# WheelPCB.net
KiCad netlist of a schematic drawn in EAGLE
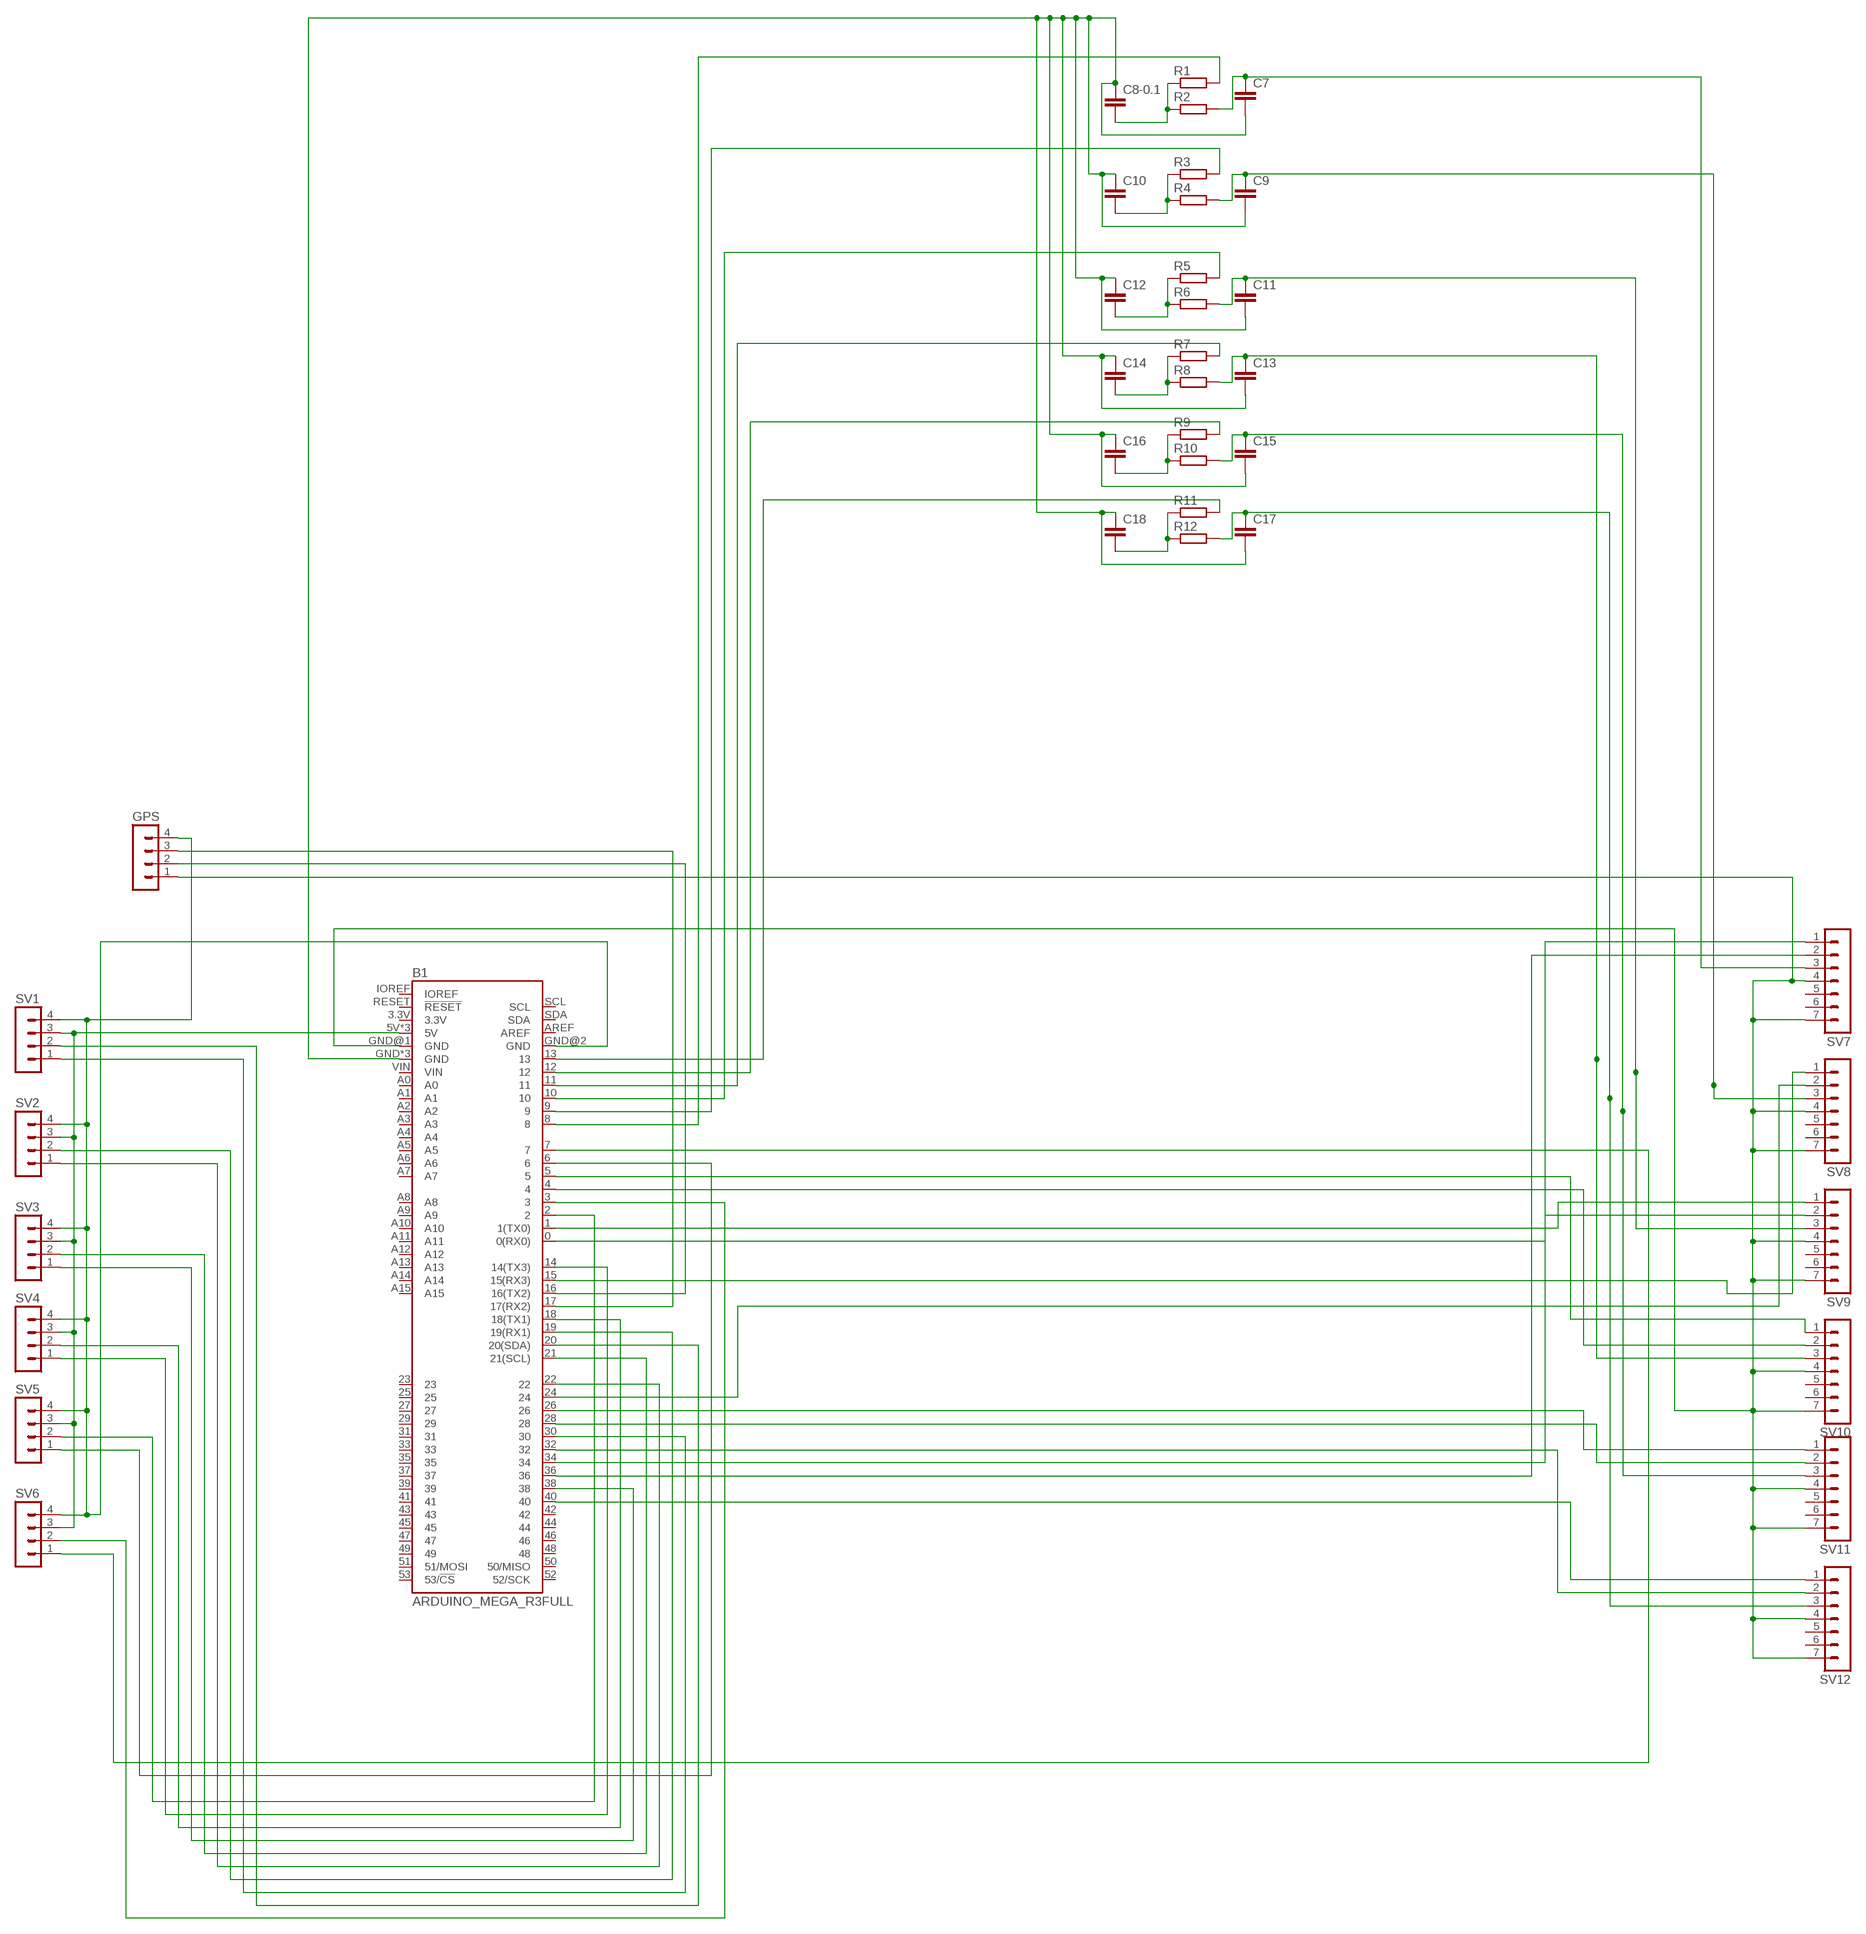
[diagram p0: schematic, sheet 1]

(export (version "E")
  (design (tool "Eeschema 10.0.6"))
  (components
    (comp (ref "B1")
      (value "ARDUINO_MEGA_R3FULL")
      (footprint "eagle-import:ARDUINO_MEGA_NO_SILK")
      (libsource (lib "eagle-import") (part "ARDUINO_MEGA_R3FULL"))
    )
    (comp (ref "C7")
      (value "C2.5/5")
      (footprint "eagle-import:C2.5-5")
      (libsource (lib "eagle-import") (part "C2.5/5"))
    )
    (comp (ref "C8-0.1")
      (value "C2.5/5")
      (footprint "eagle-import:C2.5-5")
      (libsource (lib "eagle-import") (part "C2.5/5"))
    )
    (comp (ref "C9")
      (value "C2.5/5")
      (footprint "eagle-import:C2.5-5")
      (libsource (lib "eagle-import") (part "C2.5/5"))
    )
    (comp (ref "C10")
      (value "C2.5/5")
      (footprint "eagle-import:C2.5-5")
      (libsource (lib "eagle-import") (part "C2.5/5"))
    )
    (comp (ref "C11")
      (value "C2.5/5")
      (footprint "eagle-import:C2.5-5")
      (libsource (lib "eagle-import") (part "C2.5/5"))
    )
    (comp (ref "C12")
      (value "C2.5/5")
      (footprint "eagle-import:C2.5-5")
      (libsource (lib "eagle-import") (part "C2.5/5"))
    )
    (comp (ref "C13")
      (value "C2.5/5")
      (footprint "eagle-import:C2.5-5")
      (libsource (lib "eagle-import") (part "C2.5/5"))
    )
    (comp (ref "C14")
      (value "C2.5/5")
      (footprint "eagle-import:C2.5-5")
      (libsource (lib "eagle-import") (part "C2.5/5"))
    )
    (comp (ref "C15")
      (value "C2.5/5")
      (footprint "eagle-import:C2.5-5")
      (libsource (lib "eagle-import") (part "C2.5/5"))
    )
    (comp (ref "C16")
      (value "C2.5/5")
      (footprint "eagle-import:C2.5-5")
      (libsource (lib "eagle-import") (part "C2.5/5"))
    )
    (comp (ref "C17")
      (value "C2.5/5")
      (footprint "eagle-import:C2.5-5")
      (libsource (lib "eagle-import") (part "C2.5/5"))
    )
    (comp (ref "C18")
      (value "C2.5/5")
      (footprint "eagle-import:C2.5-5")
      (libsource (lib "eagle-import") (part "C2.5/5"))
    )
    (comp (ref "GPS")
      (value "MA04-1")
      (footprint "eagle-import:MA04-1")
      (libsource (lib "eagle-import") (part "MA04-1"))
    )
    (comp (ref "R1")
      (value "R-EU_0207/10")
      (footprint "eagle-import:0207_10")
      (libsource (lib "eagle-import") (part "R-EU_0207/10"))
    )
    (comp (ref "R2")
      (value "R-EU_0207/10")
      (footprint "eagle-import:0207_10")
      (libsource (lib "eagle-import") (part "R-EU_0207/10"))
    )
    (comp (ref "R3")
      (value "R-EU_0207/10")
      (footprint "eagle-import:0207_10")
      (libsource (lib "eagle-import") (part "R-EU_0207/10"))
    )
    (comp (ref "R4")
      (value "R-EU_0207/10")
      (footprint "eagle-import:0207_10")
      (libsource (lib "eagle-import") (part "R-EU_0207/10"))
    )
    (comp (ref "R5")
      (value "R-EU_0207/10")
      (footprint "eagle-import:0207_10")
      (libsource (lib "eagle-import") (part "R-EU_0207/10"))
    )
    (comp (ref "R6")
      (value "R-EU_0207/10")
      (footprint "eagle-import:0207_10")
      (libsource (lib "eagle-import") (part "R-EU_0207/10"))
    )
    (comp (ref "R7")
      (value "R-EU_0207/10")
      (footprint "eagle-import:0207_10")
      (libsource (lib "eagle-import") (part "R-EU_0207/10"))
    )
    (comp (ref "R8")
      (value "R-EU_0207/10")
      (footprint "eagle-import:0207_10")
      (libsource (lib "eagle-import") (part "R-EU_0207/10"))
    )
    (comp (ref "R9")
      (value "R-EU_0207/10")
      (footprint "eagle-import:0207_10")
      (libsource (lib "eagle-import") (part "R-EU_0207/10"))
    )
    (comp (ref "R10")
      (value "R-EU_0207/10")
      (footprint "eagle-import:0207_10")
      (libsource (lib "eagle-import") (part "R-EU_0207/10"))
    )
    (comp (ref "R11")
      (value "R-EU_0207/10")
      (footprint "eagle-import:0207_10")
      (libsource (lib "eagle-import") (part "R-EU_0207/10"))
    )
    (comp (ref "R12")
      (value "R-EU_0207/10")
      (footprint "eagle-import:0207_10")
      (libsource (lib "eagle-import") (part "R-EU_0207/10"))
    )
    (comp (ref "SV1")
      (value "MA04-1")
      (footprint "eagle-import:MA04-1")
      (libsource (lib "eagle-import") (part "MA04-1"))
    )
    (comp (ref "SV2")
      (value "MA04-1")
      (footprint "eagle-import:MA04-1")
      (libsource (lib "eagle-import") (part "MA04-1"))
    )
    (comp (ref "SV3")
      (value "MA04-1")
      (footprint "eagle-import:MA04-1")
      (libsource (lib "eagle-import") (part "MA04-1"))
    )
    (comp (ref "SV4")
      (value "MA04-1")
      (footprint "eagle-import:MA04-1")
      (libsource (lib "eagle-import") (part "MA04-1"))
    )
    (comp (ref "SV5")
      (value "MA04-1")
      (footprint "eagle-import:MA04-1")
      (libsource (lib "eagle-import") (part "MA04-1"))
    )
    (comp (ref "SV6")
      (value "MA04-1")
      (footprint "eagle-import:MA04-1")
      (libsource (lib "eagle-import") (part "MA04-1"))
    )
    (comp (ref "SV7")
      (value "MA07-1")
      (footprint "eagle-import:MA07-1")
      (libsource (lib "eagle-import") (part "MA07-1"))
    )
    (comp (ref "SV8")
      (value "MA07-1")
      (footprint "eagle-import:MA07-1")
      (libsource (lib "eagle-import") (part "MA07-1"))
    )
    (comp (ref "SV9")
      (value "MA07-1")
      (footprint "eagle-import:MA07-1")
      (libsource (lib "eagle-import") (part "MA07-1"))
    )
    (comp (ref "SV10")
      (value "MA07-1")
      (footprint "eagle-import:MA07-1")
      (libsource (lib "eagle-import") (part "MA07-1"))
    )
    (comp (ref "SV11")
      (value "MA07-1")
      (footprint "eagle-import:MA07-1")
      (libsource (lib "eagle-import") (part "MA07-1"))
    )
    (comp (ref "SV12")
      (value "MA07-1")
      (footprint "eagle-import:MA07-1")
      (libsource (lib "eagle-import") (part "MA07-1"))
    )
  )
  (nets
    (net (code "1") (name "Net-(B1-0(RX0))") (class "Default")
      (node (ref "B1") (pin "0") (pinfunction "0(RX0)_0") (pintype "bidirectional"))
      (node (ref "SV9") (pin "2") (pinfunction "2_2") (pintype "passive"))
    )
    (net (code "2") (name "Net-(B1-1(TX0))") (class "Default")
      (node (ref "B1") (pin "1") (pinfunction "1(TX0)_1") (pintype "bidirectional"))
      (node (ref "SV9") (pin "1") (pinfunction "1_1") (pintype "passive"))
    )
    (net (code "3") (name "Net-(B1-5V-Pad5V@1)") (class "Default")
      (node (ref "B1") (pin "5V") (pinfunction "5V_5V") (pintype "bidirectional"))
      (node (ref "B1") (pin "5V@1") (pinfunction "5V_5V@1") (pintype "bidirectional"))
      (node (ref "B1") (pin "5V@2") (pinfunction "5V_5V@2") (pintype "bidirectional"))
      (node (ref "SV1") (pin "3") (pinfunction "3_3") (pintype "passive"))
      (node (ref "SV2") (pin "3") (pinfunction "3_3") (pintype "passive"))
      (node (ref "SV3") (pin "3") (pinfunction "3_3") (pintype "passive"))
      (node (ref "SV4") (pin "3") (pinfunction "3_3") (pintype "passive"))
      (node (ref "SV5") (pin "3") (pinfunction "3_3") (pintype "passive"))
      (node (ref "SV6") (pin "3") (pinfunction "3_3") (pintype "passive"))
    )
    (net (code "4") (name "Net-(B1-14(TX3))") (class "Default")
      (node (ref "B1") (pin "14") (pinfunction "14(TX3)_14") (pintype "bidirectional"))
      (node (ref "SV4") (pin "1") (pinfunction "1_1") (pintype "passive"))
    )
    (net (code "5") (name "Net-(B1-15(RX3))") (class "Default")
      (node (ref "B1") (pin "15") (pinfunction "15(RX3)_15") (pintype "bidirectional"))
      (node (ref "SV8") (pin "1") (pinfunction "1_1") (pintype "passive"))
    )
    (net (code "6") (name "Net-(B1-16(TX2))") (class "Default")
      (node (ref "B1") (pin "16") (pinfunction "16(TX2)_16") (pintype "bidirectional"))
      (node (ref "GPS") (pin "2") (pinfunction "2_2") (pintype "passive"))
    )
    (net (code "7") (name "Net-(B1-17(RX2))") (class "Default")
      (node (ref "B1") (pin "17") (pinfunction "17(RX2)_17") (pintype "bidirectional"))
      (node (ref "GPS") (pin "3") (pinfunction "3_3") (pintype "passive"))
    )
    (net (code "8") (name "Net-(B1-18(TX1))") (class "Default")
      (node (ref "B1") (pin "18") (pinfunction "18(TX1)_18") (pintype "bidirectional"))
      (node (ref "SV4") (pin "2") (pinfunction "2_2") (pintype "passive"))
    )
    (net (code "9") (name "Net-(B1-19(RX1))") (class "Default")
      (node (ref "B1") (pin "19") (pinfunction "19(RX1)_19") (pintype "bidirectional"))
      (node (ref "SV2") (pin "2") (pinfunction "2_2") (pintype "passive"))
    )
    (net (code "10") (name "Net-(B1-20(SDA))") (class "Default")
      (node (ref "B1") (pin "20") (pinfunction "20(SDA)_20") (pintype "bidirectional"))
      (node (ref "SV1") (pin "2") (pinfunction "2_2") (pintype "passive"))
    )
    (net (code "11") (name "Net-(B1-21(SCL))") (class "Default")
      (node (ref "B1") (pin "21") (pinfunction "21(SCL)_21") (pintype "bidirectional"))
      (node (ref "SV3") (pin "2") (pinfunction "2_2") (pintype "passive"))
    )
    (net (code "12") (name "Net-(B1-GND-PadGND@1)") (class "Default")
      (node (ref "B1") (pin "GND@1") (pinfunction "GND_GND@1") (pintype "bidirectional"))
      (node (ref "GPS") (pin "1") (pinfunction "1_1") (pintype "passive"))
      (node (ref "SV10") (pin "4") (pinfunction "4_4") (pintype "passive"))
      (node (ref "SV10") (pin "7") (pinfunction "7_7") (pintype "passive"))
      (node (ref "SV11") (pin "4") (pinfunction "4_4") (pintype "passive"))
      (node (ref "SV11") (pin "7") (pinfunction "7_7") (pintype "passive"))
      (node (ref "SV12") (pin "4") (pinfunction "4_4") (pintype "passive"))
      (node (ref "SV12") (pin "7") (pinfunction "7_7") (pintype "passive"))
      (node (ref "SV7") (pin "4") (pinfunction "4_4") (pintype "passive"))
      (node (ref "SV7") (pin "7") (pinfunction "7_7") (pintype "passive"))
      (node (ref "SV8") (pin "4") (pinfunction "4_4") (pintype "passive"))
      (node (ref "SV8") (pin "7") (pinfunction "7_7") (pintype "passive"))
      (node (ref "SV9") (pin "4") (pinfunction "4_4") (pintype "passive"))
      (node (ref "SV9") (pin "7") (pinfunction "7_7") (pintype "passive"))
    )
    (net (code "13") (name "Net-(B1-GND-PadGND@2)") (class "Default")
      (node (ref "B1") (pin "GND@2") (pinfunction "GND_GND@2") (pintype "bidirectional"))
      (node (ref "GPS") (pin "4") (pinfunction "4_4") (pintype "passive"))
      (node (ref "SV1") (pin "4") (pinfunction "4_4") (pintype "passive"))
      (node (ref "SV2") (pin "4") (pinfunction "4_4") (pintype "passive"))
      (node (ref "SV3") (pin "4") (pinfunction "4_4") (pintype "passive"))
      (node (ref "SV4") (pin "4") (pinfunction "4_4") (pintype "passive"))
      (node (ref "SV5") (pin "4") (pinfunction "4_4") (pintype "passive"))
      (node (ref "SV6") (pin "4") (pinfunction "4_4") (pintype "passive"))
    )
    (net (code "14") (name "Net-(B1-GND-PadGND@3)") (class "Default")
      (node (ref "B1") (pin "GND") (pinfunction "GND_GND") (pintype "bidirectional"))
      (node (ref "B1") (pin "GND@3") (pinfunction "GND_GND@3") (pintype "bidirectional"))
      (node (ref "B1") (pin "GND@4") (pinfunction "GND_GND@4") (pintype "bidirectional"))
      (node (ref "C10") (pin "1") (pinfunction "1_1") (pintype "passive"))
      (node (ref "C11") (pin "2") (pinfunction "2_2") (pintype "passive"))
      (node (ref "C12") (pin "1") (pinfunction "1_1") (pintype "passive"))
      (node (ref "C13") (pin "2") (pinfunction "2_2") (pintype "passive"))
      (node (ref "C14") (pin "1") (pinfunction "1_1") (pintype "passive"))
      (node (ref "C15") (pin "2") (pinfunction "2_2") (pintype "passive"))
      (node (ref "C16") (pin "1") (pinfunction "1_1") (pintype "passive"))
      (node (ref "C17") (pin "2") (pinfunction "2_2") (pintype "passive"))
      (node (ref "C18") (pin "1") (pinfunction "1_1") (pintype "passive"))
      (node (ref "C7") (pin "2") (pinfunction "2_2") (pintype "passive"))
      (node (ref "C8-0.1") (pin "1") (pinfunction "1_1") (pintype "passive"))
      (node (ref "C9") (pin "2") (pinfunction "2_2") (pintype "passive"))
    )
    (net (code "15") (name "Net-(B1-Pad2)") (class "Default")
      (node (ref "B1") (pin "2") (pinfunction "2_2") (pintype "bidirectional"))
      (node (ref "SV5") (pin "2") (pinfunction "2_2") (pintype "passive"))
    )
    (net (code "16") (name "Net-(B1-Pad3)") (class "Default")
      (node (ref "B1") (pin "3") (pinfunction "3_3") (pintype "bidirectional"))
      (node (ref "SV6") (pin "2") (pinfunction "2_2") (pintype "passive"))
    )
    (net (code "17") (name "Net-(B1-Pad4)") (class "Default")
      (node (ref "B1") (pin "4") (pinfunction "4_4") (pintype "bidirectional"))
      (node (ref "SV10") (pin "2") (pinfunction "2_2") (pintype "passive"))
    )
    (net (code "18") (name "Net-(B1-Pad5)") (class "Default")
      (node (ref "B1") (pin "5") (pinfunction "5_5") (pintype "bidirectional"))
      (node (ref "SV10") (pin "1") (pinfunction "1_1") (pintype "passive"))
    )
    (net (code "19") (name "Net-(B1-Pad6)") (class "Default")
      (node (ref "B1") (pin "6") (pinfunction "6_6") (pintype "bidirectional"))
      (node (ref "SV5") (pin "1") (pinfunction "1_1") (pintype "passive"))
    )
    (net (code "20") (name "Net-(B1-Pad7)") (class "Default")
      (node (ref "B1") (pin "7") (pinfunction "7_7") (pintype "bidirectional"))
      (node (ref "SV6") (pin "1") (pinfunction "1_1") (pintype "passive"))
    )
    (net (code "21") (name "Net-(B1-Pad8)") (class "Default")
      (node (ref "B1") (pin "8") (pinfunction "8_8") (pintype "bidirectional"))
      (node (ref "R1") (pin "2") (pinfunction "2_2") (pintype "passive"))
    )
    (net (code "22") (name "Net-(B1-Pad9)") (class "Default")
      (node (ref "B1") (pin "9") (pinfunction "9_9") (pintype "bidirectional"))
      (node (ref "R3") (pin "2") (pinfunction "2_2") (pintype "passive"))
    )
    (net (code "23") (name "Net-(B1-Pad10)") (class "Default")
      (node (ref "B1") (pin "10") (pinfunction "10_10") (pintype "bidirectional"))
      (node (ref "R5") (pin "2") (pinfunction "2_2") (pintype "passive"))
    )
    (net (code "24") (name "Net-(B1-Pad11)") (class "Default")
      (node (ref "B1") (pin "11") (pinfunction "11_11") (pintype "bidirectional"))
      (node (ref "R7") (pin "2") (pinfunction "2_2") (pintype "passive"))
    )
    (net (code "25") (name "Net-(B1-Pad12)") (class "Default")
      (node (ref "B1") (pin "12") (pinfunction "12_12") (pintype "bidirectional"))
      (node (ref "R9") (pin "2") (pinfunction "2_2") (pintype "passive"))
    )
    (net (code "26") (name "Net-(B1-Pad13)") (class "Default")
      (node (ref "B1") (pin "13") (pinfunction "13_13") (pintype "bidirectional"))
      (node (ref "R11") (pin "2") (pinfunction "2_2") (pintype "passive"))
    )
    (net (code "27") (name "Net-(B1-Pad22)") (class "Default")
      (node (ref "B1") (pin "22") (pinfunction "22_22") (pintype "bidirectional"))
      (node (ref "SV2") (pin "1") (pinfunction "1_1") (pintype "passive"))
    )
    (net (code "28") (name "Net-(B1-Pad24)") (class "Default")
      (node (ref "B1") (pin "24") (pinfunction "24_24") (pintype "bidirectional"))
      (node (ref "SV8") (pin "2") (pinfunction "2_2") (pintype "passive"))
    )
    (net (code "29") (name "Net-(B1-Pad26)") (class "Default")
      (node (ref "B1") (pin "26") (pinfunction "26_26") (pintype "bidirectional"))
      (node (ref "SV11") (pin "1") (pinfunction "1_1") (pintype "passive"))
    )
    (net (code "30") (name "Net-(B1-Pad28)") (class "Default")
      (node (ref "B1") (pin "28") (pinfunction "28_28") (pintype "bidirectional"))
      (node (ref "SV11") (pin "2") (pinfunction "2_2") (pintype "passive"))
    )
    (net (code "31") (name "Net-(B1-Pad30)") (class "Default")
      (node (ref "B1") (pin "30") (pinfunction "30_30") (pintype "bidirectional"))
      (node (ref "SV1") (pin "1") (pinfunction "1_1") (pintype "passive"))
    )
    (net (code "32") (name "Net-(B1-Pad32)") (class "Default")
      (node (ref "B1") (pin "32") (pinfunction "32_32") (pintype "bidirectional"))
      (node (ref "SV12") (pin "2") (pinfunction "2_2") (pintype "passive"))
    )
    (net (code "33") (name "Net-(B1-Pad34)") (class "Default")
      (node (ref "B1") (pin "34") (pinfunction "34_34") (pintype "bidirectional"))
      (node (ref "SV7") (pin "1") (pinfunction "1_1") (pintype "passive"))
    )
    (net (code "34") (name "Net-(B1-Pad36)") (class "Default")
      (node (ref "B1") (pin "36") (pinfunction "36_36") (pintype "bidirectional"))
      (node (ref "SV7") (pin "2") (pinfunction "2_2") (pintype "passive"))
    )
    (net (code "35") (name "Net-(B1-Pad38)") (class "Default")
      (node (ref "B1") (pin "38") (pinfunction "38_38") (pintype "bidirectional"))
      (node (ref "SV3") (pin "1") (pinfunction "1_1") (pintype "passive"))
    )
    (net (code "36") (name "Net-(B1-Pad40)") (class "Default")
      (node (ref "B1") (pin "40") (pinfunction "40_40") (pintype "bidirectional"))
      (node (ref "SV12") (pin "1") (pinfunction "1_1") (pintype "passive"))
    )
    (net (code "37") (name "Net-(C7-Pad1)") (class "Default")
      (node (ref "C7") (pin "1") (pinfunction "1_1") (pintype "passive"))
      (node (ref "R2") (pin "2") (pinfunction "2_2") (pintype "passive"))
      (node (ref "SV7") (pin "3") (pinfunction "3_3") (pintype "passive"))
    )
    (net (code "38") (name "Net-(C8-0.1-Pad2)") (class "Default")
      (node (ref "C8-0.1") (pin "2") (pinfunction "2_2") (pintype "passive"))
      (node (ref "R1") (pin "1") (pinfunction "1_1") (pintype "passive"))
      (node (ref "R2") (pin "1") (pinfunction "1_1") (pintype "passive"))
    )
    (net (code "39") (name "Net-(C9-Pad1)") (class "Default")
      (node (ref "C9") (pin "1") (pinfunction "1_1") (pintype "passive"))
      (node (ref "R4") (pin "2") (pinfunction "2_2") (pintype "passive"))
      (node (ref "SV8") (pin "3") (pinfunction "3_3") (pintype "passive"))
    )
    (net (code "40") (name "Net-(C10-Pad2)") (class "Default")
      (node (ref "C10") (pin "2") (pinfunction "2_2") (pintype "passive"))
      (node (ref "R3") (pin "1") (pinfunction "1_1") (pintype "passive"))
      (node (ref "R4") (pin "1") (pinfunction "1_1") (pintype "passive"))
    )
    (net (code "41") (name "Net-(C11-Pad1)") (class "Default")
      (node (ref "C11") (pin "1") (pinfunction "1_1") (pintype "passive"))
      (node (ref "R6") (pin "2") (pinfunction "2_2") (pintype "passive"))
      (node (ref "SV9") (pin "3") (pinfunction "3_3") (pintype "passive"))
    )
    (net (code "42") (name "Net-(C12-Pad2)") (class "Default")
      (node (ref "C12") (pin "2") (pinfunction "2_2") (pintype "passive"))
      (node (ref "R5") (pin "1") (pinfunction "1_1") (pintype "passive"))
      (node (ref "R6") (pin "1") (pinfunction "1_1") (pintype "passive"))
    )
    (net (code "43") (name "Net-(C13-Pad1)") (class "Default")
      (node (ref "C13") (pin "1") (pinfunction "1_1") (pintype "passive"))
      (node (ref "R8") (pin "2") (pinfunction "2_2") (pintype "passive"))
      (node (ref "SV10") (pin "3") (pinfunction "3_3") (pintype "passive"))
    )
    (net (code "44") (name "Net-(C14-Pad2)") (class "Default")
      (node (ref "C14") (pin "2") (pinfunction "2_2") (pintype "passive"))
      (node (ref "R7") (pin "1") (pinfunction "1_1") (pintype "passive"))
      (node (ref "R8") (pin "1") (pinfunction "1_1") (pintype "passive"))
    )
    (net (code "45") (name "Net-(C15-Pad1)") (class "Default")
      (node (ref "C15") (pin "1") (pinfunction "1_1") (pintype "passive"))
      (node (ref "R10") (pin "2") (pinfunction "2_2") (pintype "passive"))
      (node (ref "SV11") (pin "3") (pinfunction "3_3") (pintype "passive"))
    )
    (net (code "46") (name "Net-(C16-Pad2)") (class "Default")
      (node (ref "C16") (pin "2") (pinfunction "2_2") (pintype "passive"))
      (node (ref "R10") (pin "1") (pinfunction "1_1") (pintype "passive"))
      (node (ref "R9") (pin "1") (pinfunction "1_1") (pintype "passive"))
    )
    (net (code "47") (name "Net-(C17-Pad1)") (class "Default")
      (node (ref "C17") (pin "1") (pinfunction "1_1") (pintype "passive"))
      (node (ref "R12") (pin "2") (pinfunction "2_2") (pintype "passive"))
      (node (ref "SV12") (pin "3") (pinfunction "3_3") (pintype "passive"))
    )
    (net (code "48") (name "Net-(C18-Pad2)") (class "Default")
      (node (ref "C18") (pin "2") (pinfunction "2_2") (pintype "passive"))
      (node (ref "R11") (pin "1") (pinfunction "1_1") (pintype "passive"))
      (node (ref "R12") (pin "1") (pinfunction "1_1") (pintype "passive"))
    )
    (net (code "49") (name "unconnected-(B1-50{slash}MISO-Pad50)") (class "Default")
      (node (ref "B1") (pin "50") (pinfunction "50/MISO_50") (pintype "bidirectional"))
    )
    (net (code "50") (name "unconnected-(B1-51{slash}MOSI-Pad51)") (class "Default")
      (node (ref "B1") (pin "51") (pinfunction "51/MOSI_51") (pintype "bidirectional"))
    )
    (net (code "51") (name "unconnected-(B1-52{slash}SCK-Pad52)") (class "Default")
      (node (ref "B1") (pin "52") (pinfunction "52/SCK_52") (pintype "bidirectional"))
    )
    (net (code "52") (name "unconnected-(B1-53{slash}~{CS}-Pad53)") (class "Default")
      (node (ref "B1") (pin "53") (pinfunction "53/~{CS}_53") (pintype "bidirectional"))
    )
    (net (code "53") (name "unconnected-(B1-Pad3.3V)") (class "Default")
      (node (ref "B1") (pin "3.3V") (pinfunction "3.3V_3.3V") (pintype "bidirectional"))
    )
    (net (code "54") (name "unconnected-(B1-Pad23)") (class "Default")
      (node (ref "B1") (pin "23") (pinfunction "23_23") (pintype "bidirectional"))
    )
    (net (code "55") (name "unconnected-(B1-Pad25)") (class "Default")
      (node (ref "B1") (pin "25") (pinfunction "25_25") (pintype "bidirectional"))
    )
    (net (code "56") (name "unconnected-(B1-Pad27)") (class "Default")
      (node (ref "B1") (pin "27") (pinfunction "27_27") (pintype "bidirectional"))
    )
    (net (code "57") (name "unconnected-(B1-Pad29)") (class "Default")
      (node (ref "B1") (pin "29") (pinfunction "29_29") (pintype "bidirectional"))
    )
    (net (code "58") (name "unconnected-(B1-Pad31)") (class "Default")
      (node (ref "B1") (pin "31") (pinfunction "31_31") (pintype "bidirectional"))
    )
    (net (code "59") (name "unconnected-(B1-Pad33)") (class "Default")
      (node (ref "B1") (pin "33") (pinfunction "33_33") (pintype "bidirectional"))
    )
    (net (code "60") (name "unconnected-(B1-Pad35)") (class "Default")
      (node (ref "B1") (pin "35") (pinfunction "35_35") (pintype "bidirectional"))
    )
    (net (code "61") (name "unconnected-(B1-Pad37)") (class "Default")
      (node (ref "B1") (pin "37") (pinfunction "37_37") (pintype "bidirectional"))
    )
    (net (code "62") (name "unconnected-(B1-Pad39)") (class "Default")
      (node (ref "B1") (pin "39") (pinfunction "39_39") (pintype "bidirectional"))
    )
    (net (code "63") (name "unconnected-(B1-Pad41)") (class "Default")
      (node (ref "B1") (pin "41") (pinfunction "41_41") (pintype "bidirectional"))
    )
    (net (code "64") (name "unconnected-(B1-Pad42)") (class "Default")
      (node (ref "B1") (pin "42") (pinfunction "42_42") (pintype "bidirectional"))
    )
    (net (code "65") (name "unconnected-(B1-Pad43)") (class "Default")
      (node (ref "B1") (pin "43") (pinfunction "43_43") (pintype "bidirectional"))
    )
    (net (code "66") (name "unconnected-(B1-Pad44)") (class "Default")
      (node (ref "B1") (pin "44") (pinfunction "44_44") (pintype "bidirectional"))
    )
    (net (code "67") (name "unconnected-(B1-Pad45)") (class "Default")
      (node (ref "B1") (pin "45") (pinfunction "45_45") (pintype "bidirectional"))
    )
    (net (code "68") (name "unconnected-(B1-Pad46)") (class "Default")
      (node (ref "B1") (pin "46") (pinfunction "46_46") (pintype "bidirectional"))
    )
    (net (code "69") (name "unconnected-(B1-Pad47)") (class "Default")
      (node (ref "B1") (pin "47") (pinfunction "47_47") (pintype "bidirectional"))
    )
    (net (code "70") (name "unconnected-(B1-Pad48)") (class "Default")
      (node (ref "B1") (pin "48") (pinfunction "48_48") (pintype "bidirectional"))
    )
    (net (code "71") (name "unconnected-(B1-Pad49)") (class "Default")
      (node (ref "B1") (pin "49") (pinfunction "49_49") (pintype "bidirectional"))
    )
    (net (code "72") (name "unconnected-(B1-PadA0)") (class "Default")
      (node (ref "B1") (pin "A0") (pinfunction "A0_A0") (pintype "bidirectional"))
    )
    (net (code "73") (name "unconnected-(B1-PadA1)") (class "Default")
      (node (ref "B1") (pin "A1") (pinfunction "A1_A1") (pintype "bidirectional"))
    )
    (net (code "74") (name "unconnected-(B1-PadA2)") (class "Default")
      (node (ref "B1") (pin "A2") (pinfunction "A2_A2") (pintype "bidirectional"))
    )
    (net (code "75") (name "unconnected-(B1-PadA3)") (class "Default")
      (node (ref "B1") (pin "A3") (pinfunction "A3_A3") (pintype "bidirectional"))
    )
    (net (code "76") (name "unconnected-(B1-PadA4)") (class "Default")
      (node (ref "B1") (pin "A4") (pinfunction "A4_A4") (pintype "bidirectional"))
    )
    (net (code "77") (name "unconnected-(B1-PadA5)") (class "Default")
      (node (ref "B1") (pin "A5") (pinfunction "A5_A5") (pintype "bidirectional"))
    )
    (net (code "78") (name "unconnected-(B1-PadA6)") (class "Default")
      (node (ref "B1") (pin "A6") (pinfunction "A6_A6") (pintype "bidirectional"))
    )
    (net (code "79") (name "unconnected-(B1-PadA7)") (class "Default")
      (node (ref "B1") (pin "A7") (pinfunction "A7_A7") (pintype "bidirectional"))
    )
    (net (code "80") (name "unconnected-(B1-PadA8)") (class "Default")
      (node (ref "B1") (pin "A8") (pinfunction "A8_A8") (pintype "bidirectional"))
    )
    (net (code "81") (name "unconnected-(B1-PadA9)") (class "Default")
      (node (ref "B1") (pin "A9") (pinfunction "A9_A9") (pintype "bidirectional"))
    )
    (net (code "82") (name "unconnected-(B1-PadA10)") (class "Default")
      (node (ref "B1") (pin "A10") (pinfunction "A10_A10") (pintype "bidirectional"))
    )
    (net (code "83") (name "unconnected-(B1-PadA11)") (class "Default")
      (node (ref "B1") (pin "A11") (pinfunction "A11_A11") (pintype "bidirectional"))
    )
    (net (code "84") (name "unconnected-(B1-PadA12)") (class "Default")
      (node (ref "B1") (pin "A12") (pinfunction "A12_A12") (pintype "bidirectional"))
    )
    (net (code "85") (name "unconnected-(B1-PadA13)") (class "Default")
      (node (ref "B1") (pin "A13") (pinfunction "A13_A13") (pintype "bidirectional"))
    )
    (net (code "86") (name "unconnected-(B1-PadA14)") (class "Default")
      (node (ref "B1") (pin "A14") (pinfunction "A14_A14") (pintype "bidirectional"))
    )
    (net (code "87") (name "unconnected-(B1-PadA15)") (class "Default")
      (node (ref "B1") (pin "A15") (pinfunction "A15_A15") (pintype "bidirectional"))
    )
    (net (code "88") (name "unconnected-(B1-PadAREF)") (class "Default")
      (node (ref "B1") (pin "AREF") (pinfunction "AREF_AREF") (pintype "bidirectional"))
    )
    (net (code "89") (name "unconnected-(B1-PadIOREF)") (class "Default")
      (node (ref "B1") (pin "IOREF") (pinfunction "IOREF_IOREF") (pintype "bidirectional"))
    )
    (net (code "90") (name "unconnected-(B1-PadSCL)") (class "Default")
      (node (ref "B1") (pin "SCL") (pinfunction "SCL_SCL") (pintype "bidirectional"))
    )
    (net (code "91") (name "unconnected-(B1-PadSDA)") (class "Default")
      (node (ref "B1") (pin "SDA") (pinfunction "SDA_SDA") (pintype "bidirectional"))
    )
    (net (code "92") (name "unconnected-(B1-PadVIN)") (class "Default")
      (node (ref "B1") (pin "VIN") (pinfunction "VIN_VIN") (pintype "bidirectional"))
    )
    (net (code "93") (name "unconnected-(B1-~{RESET}-PadRESET)") (class "Default")
      (node (ref "B1") (pin "RESET") (pinfunction "~{RESET}_RESET") (pintype "bidirectional"))
    )
    (net (code "94") (name "unconnected-(SV7-Pad5)") (class "Default")
      (node (ref "SV7") (pin "5") (pinfunction "5_5") (pintype "passive"))
    )
    (net (code "95") (name "unconnected-(SV7-Pad6)") (class "Default")
      (node (ref "SV7") (pin "6") (pinfunction "6_6") (pintype "passive"))
    )
    (net (code "96") (name "unconnected-(SV8-Pad5)") (class "Default")
      (node (ref "SV8") (pin "5") (pinfunction "5_5") (pintype "passive"))
    )
    (net (code "97") (name "unconnected-(SV8-Pad6)") (class "Default")
      (node (ref "SV8") (pin "6") (pinfunction "6_6") (pintype "passive"))
    )
    (net (code "98") (name "unconnected-(SV9-Pad5)") (class "Default")
      (node (ref "SV9") (pin "5") (pinfunction "5_5") (pintype "passive"))
    )
    (net (code "99") (name "unconnected-(SV9-Pad6)") (class "Default")
      (node (ref "SV9") (pin "6") (pinfunction "6_6") (pintype "passive"))
    )
    (net (code "100") (name "unconnected-(SV10-Pad5)") (class "Default")
      (node (ref "SV10") (pin "5") (pinfunction "5_5") (pintype "passive"))
    )
    (net (code "101") (name "unconnected-(SV10-Pad6)") (class "Default")
      (node (ref "SV10") (pin "6") (pinfunction "6_6") (pintype "passive"))
    )
    (net (code "102") (name "unconnected-(SV11-Pad5)") (class "Default")
      (node (ref "SV11") (pin "5") (pinfunction "5_5") (pintype "passive"))
    )
    (net (code "103") (name "unconnected-(SV11-Pad6)") (class "Default")
      (node (ref "SV11") (pin "6") (pinfunction "6_6") (pintype "passive"))
    )
    (net (code "104") (name "unconnected-(SV12-Pad5)") (class "Default")
      (node (ref "SV12") (pin "5") (pinfunction "5_5") (pintype "passive"))
    )
    (net (code "105") (name "unconnected-(SV12-Pad6)") (class "Default")
      (node (ref "SV12") (pin "6") (pinfunction "6_6") (pintype "passive"))
    )
  )
)
